# 10_Speed.net
KiCad netlist of a schematic drawn in Altium Designer
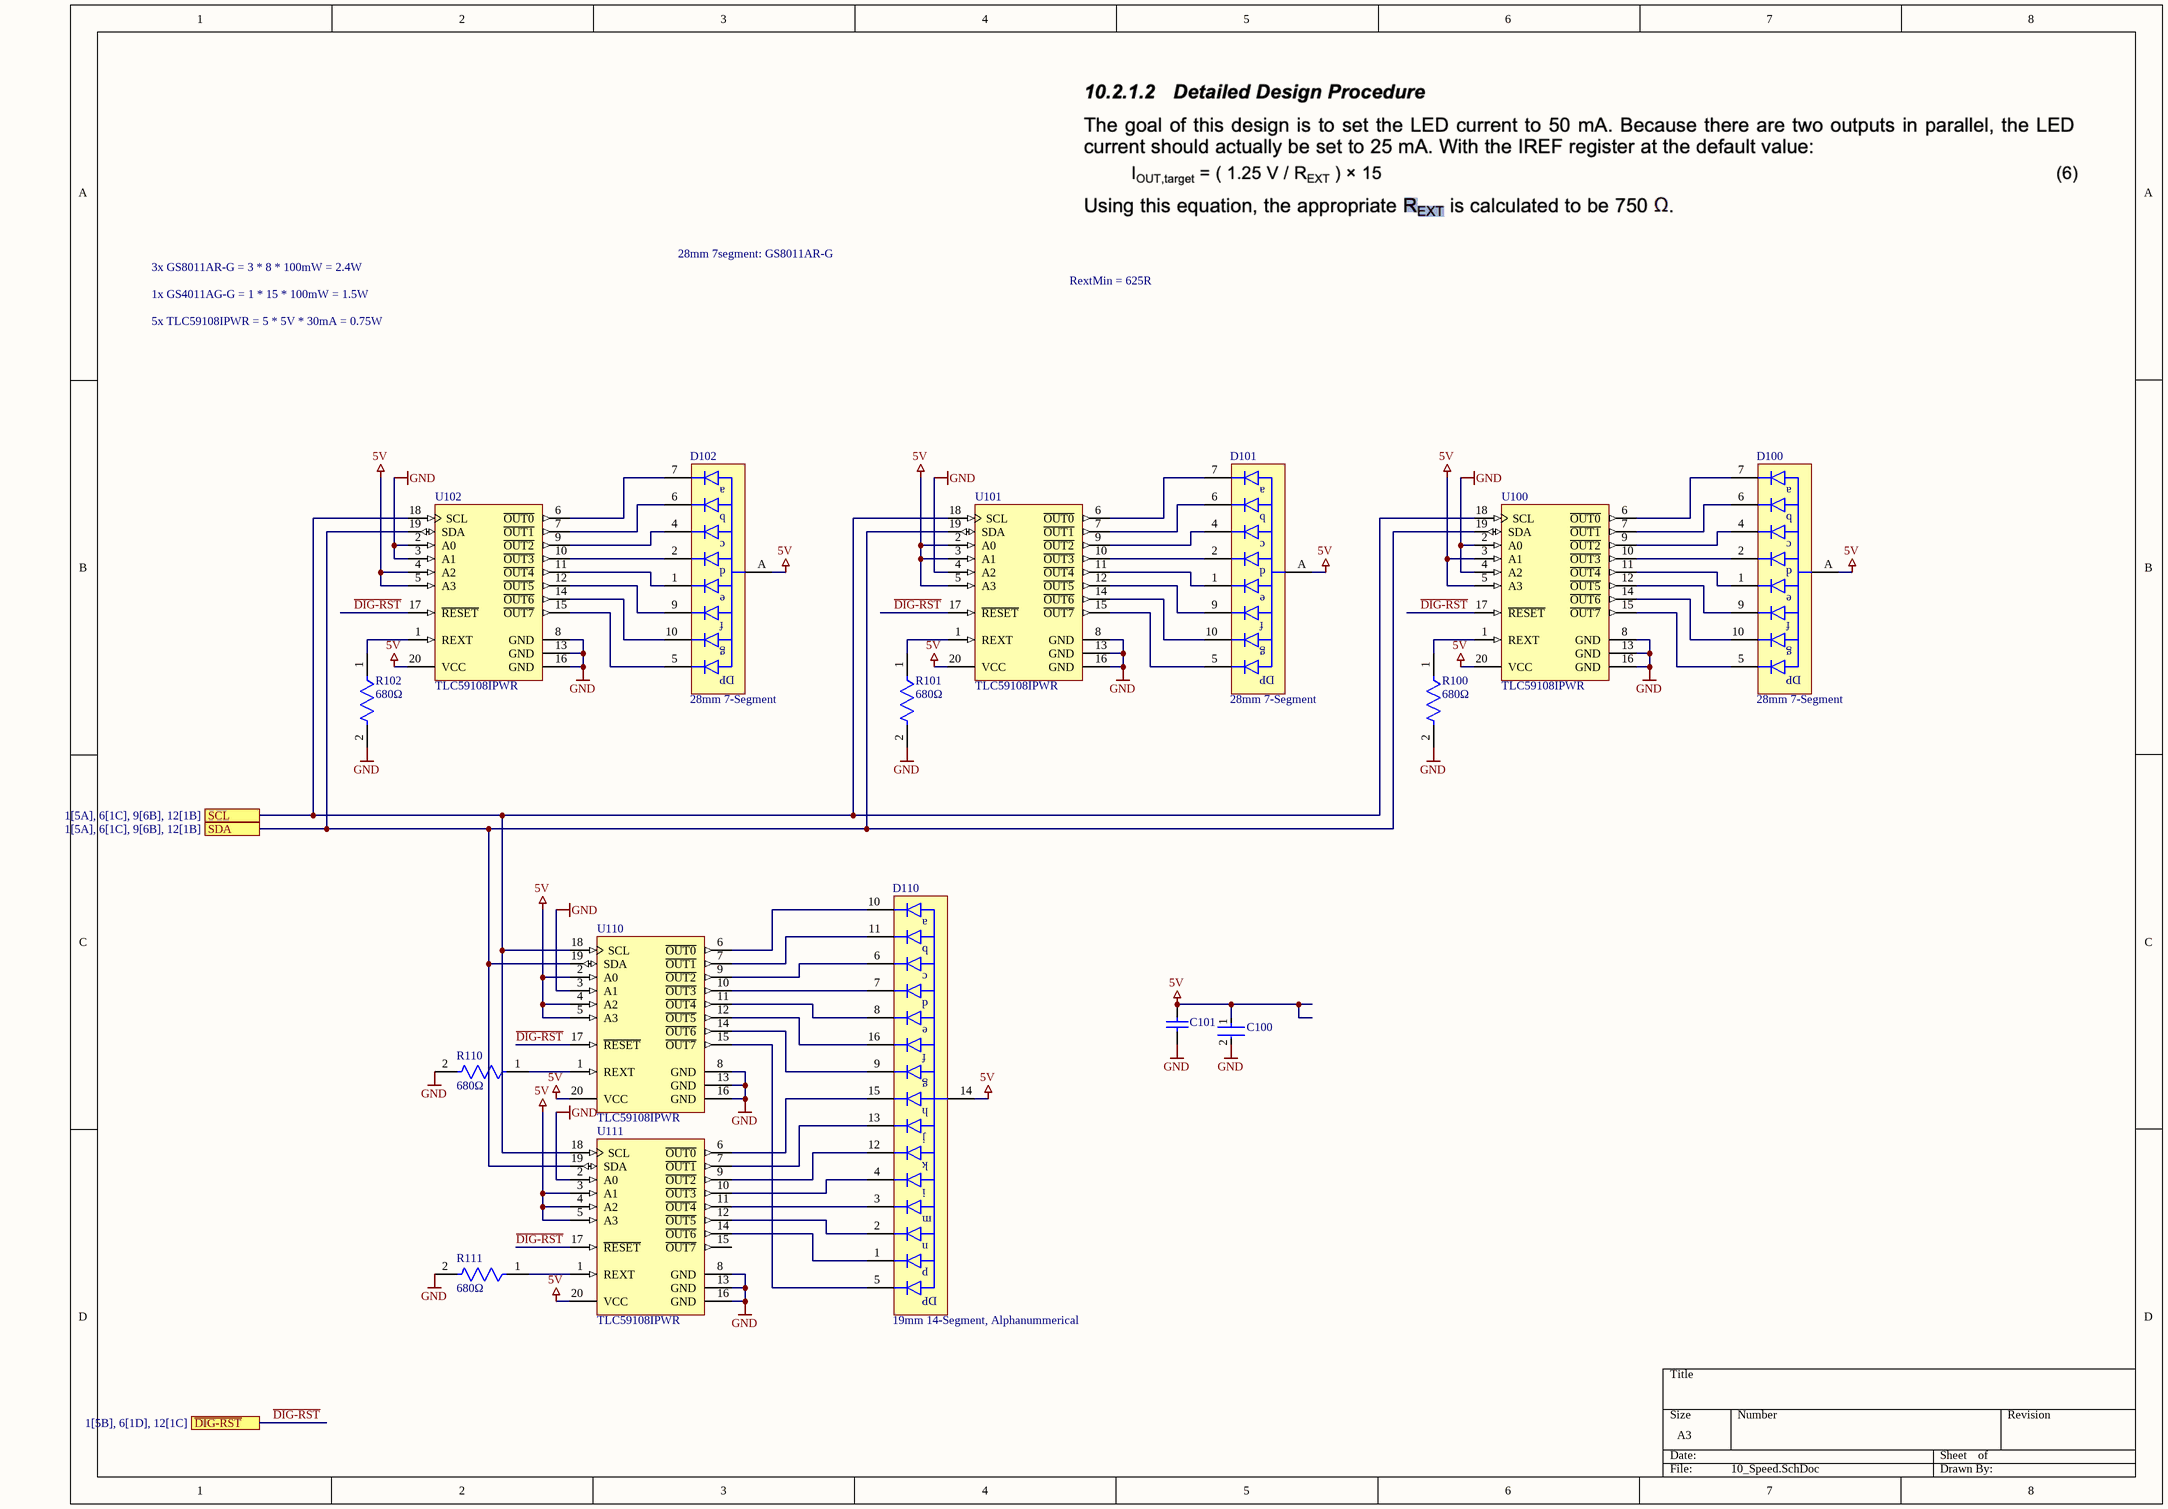
[diagram p0: 10_Speed.SchDoc]

(export (version "E")
  (design (tool "Eeschema 10.0.6"))
  (components
    (comp (ref "C100")
      (value "GMK107BJ104KAHT")
      (footprint "FP-0603-L_1_6_0_1-W_0_8_0-IPC_B")
      (description "Ceramic Capacitor Automotive 0.1uF ±10% 35V X5R 0603")
      (fields (field (name "TOLERANCE") "10%"))
      (libsource (lib "Altium Content Vault") (part "02cd4be3c70576c341d710602a673aa"))
    )
    (comp (ref "C101")
      (value "CAP 47uF 10V 1206(3216)")
      (footprint "CAPC1206(3216)190_N")
      (description "CAP 47uF 10V ±20% 1206 (3216 Metric) Thickness 1.9mm SMD")
      (fields (field (name "TOLERANCE") "Â±20%"))
      (libsource (lib "Altium Content Vault") (part "CAP"))
    )
    (comp (ref "D100")
      (value "28mm 7-Segment")
      (footprint "GS8011AR-G")
      (description "SMD, 28x16.8mm 7-Segment")
      (libsource (lib "AltiumLib_MILUTIN") (part "GS8011AR-G"))
    )
    (comp (ref "D101")
      (value "28mm 7-Segment")
      (footprint "GS8011AR-G")
      (description "SMD, 28x16.8mm 7-Segment")
      (libsource (lib "AltiumLib_MILUTIN") (part "GS8011AR-G"))
    )
    (comp (ref "D102")
      (value "28mm 7-Segment")
      (footprint "GS8011AR-G")
      (description "SMD, 28x16.8mm 7-Segment")
      (libsource (lib "AltiumLib_MILUTIN") (part "GS8011AR-G"))
    )
    (comp (ref "D110")
      (value "19mm 14-Segment, Alphanummerical")
      (footprint "GS4011AG-G")
      (description "SMD, 19x9.3mm 14-Segment, Alphanummerical")
      (libsource (lib "AltiumLib_MILUTIN") (part "GS4011AG-G"))
    )
    (comp (ref "R100")
      (value "680Ω")
      (footprint "FP-CRCW0603-e3-IPC_A")
      (description "RES Thick Film, 680Ω, 5%, 0.1W, 200ppm/°C, 0603\r\nCRCW0603680RJNEA")
      (fields (field (name "TOLERANCE") "5%"))
      (libsource (lib "Altium Content Vault") (part "1029c3af85768c4190bb7ad29bc67b5"))
    )
    (comp (ref "R101")
      (value "680Ω")
      (footprint "FP-CRCW0603-e3-IPC_A")
      (description "RES Thick Film, 680Ω, 5%, 0.1W, 200ppm/°C, 0603\r\nCRCW0603680RJNEA")
      (fields (field (name "TOLERANCE") "5%"))
      (libsource (lib "Altium Content Vault") (part "1029c3af85768c4190bb7ad29bc67b5"))
    )
    (comp (ref "R102")
      (value "680Ω")
      (footprint "FP-CRCW0603-e3-IPC_A")
      (description "RES Thick Film, 680Ω, 5%, 0.1W, 200ppm/°C, 0603\r\nCRCW0603680RJNEA")
      (fields (field (name "TOLERANCE") "5%"))
      (libsource (lib "Altium Content Vault") (part "1029c3af85768c4190bb7ad29bc67b5"))
    )
    (comp (ref "R110")
      (value "680Ω")
      (footprint "FP-CRCW0603-e3-IPC_A")
      (description "RES Thick Film, 680Ω, 5%, 0.1W, 200ppm/°C, 0603\r\nCRCW0603680RJNEA")
      (fields (field (name "TOLERANCE") "5%"))
      (libsource (lib "Altium Content Vault") (part "1029c3af85768c4190bb7ad29bc67b5"))
    )
    (comp (ref "R111")
      (value "680Ω")
      (footprint "FP-CRCW0603-e3-IPC_A")
      (description "RES Thick Film, 680Ω, 5%, 0.1W, 200ppm/°C, 0603\r\nCRCW0603680RJNEA")
      (fields (field (name "TOLERANCE") "5%"))
      (libsource (lib "Altium Content Vault") (part "1029c3af85768c4190bb7ad29bc67b5"))
    )
    (comp (ref "U100")
      (value "TLC59108IPWR")
      (footprint "PW0020A_M")
      (fields (field (name "MANUFACTURER") "Texas Instruments"))
      (libsource (lib "Altium Content Vault") (part "TI-TLC59108PW20"))
    )
    (comp (ref "U101")
      (value "TLC59108IPWR")
      (footprint "PW0020A_M")
      (fields (field (name "MANUFACTURER") "Texas Instruments"))
      (libsource (lib "Altium Content Vault") (part "TI-TLC59108PW20"))
    )
    (comp (ref "U102")
      (value "TLC59108IPWR")
      (footprint "PW0020A_M")
      (fields (field (name "MANUFACTURER") "Texas Instruments"))
      (libsource (lib "Altium Content Vault") (part "TI-TLC59108PW20"))
    )
    (comp (ref "U110")
      (value "TLC59108IPWR")
      (footprint "PW0020A_M")
      (fields (field (name "MANUFACTURER") "Texas Instruments"))
      (libsource (lib "Altium Content Vault") (part "TI-TLC59108PW20"))
    )
    (comp (ref "U111")
      (value "TLC59108IPWR")
      (footprint "PW0020A_M")
      (fields (field (name "MANUFACTURER") "Texas Instruments"))
      (libsource (lib "Altium Content Vault") (part "TI-TLC59108PW20"))
    )
  )
  (nets
    (net (code "1") (name "/SCL") (class "Default")
      (node (ref "U100") (pin "18") (pinfunction "SCL_18") (pintype "input"))
      (node (ref "U101") (pin "18") (pinfunction "SCL_18") (pintype "input"))
      (node (ref "U102") (pin "18") (pinfunction "SCL_18") (pintype "input"))
      (node (ref "U110") (pin "18") (pinfunction "SCL_18") (pintype "input"))
      (node (ref "U111") (pin "18") (pinfunction "SCL_18") (pintype "input"))
    )
    (net (code "2") (name "/SDA") (class "Default")
      (node (ref "U100") (pin "19") (pinfunction "SDA_19") (pintype "bidirectional"))
      (node (ref "U101") (pin "19") (pinfunction "SDA_19") (pintype "bidirectional"))
      (node (ref "U102") (pin "19") (pinfunction "SDA_19") (pintype "bidirectional"))
      (node (ref "U110") (pin "19") (pinfunction "SDA_19") (pintype "bidirectional"))
      (node (ref "U111") (pin "19") (pinfunction "SDA_19") (pintype "bidirectional"))
    )
    (net (code "3") (name "/~{DIG-RST}") (class "Default")
      (node (ref "U100") (pin "17") (pinfunction "~{RESET}_17") (pintype "input"))
      (node (ref "U101") (pin "17") (pinfunction "~{RESET}_17") (pintype "input"))
      (node (ref "U102") (pin "17") (pinfunction "~{RESET}_17") (pintype "input"))
      (node (ref "U110") (pin "17") (pinfunction "~{RESET}_17") (pintype "input"))
      (node (ref "U111") (pin "17") (pinfunction "~{RESET}_17") (pintype "input"))
    )
    (net (code "4") (name "5V") (class "Default")
      (node (ref "C100") (pin "1") (pinfunction "1_1") (pintype "passive"))
      (node (ref "C101") (pin "2") (pinfunction "2_2") (pintype "passive"))
      (node (ref "D100") (pin "A") (pinfunction "A_A") (pintype "passive"))
      (node (ref "D101") (pin "A") (pinfunction "A_A") (pintype "passive"))
      (node (ref "D102") (pin "A") (pinfunction "A_A") (pintype "passive"))
      (node (ref "D110") (pin "14") (pinfunction "14_14") (pintype "passive"))
      (node (ref "U100") (pin "20") (pinfunction "VCC_20") (pintype "power_in"))
      (node (ref "U100") (pin "3") (pinfunction "A1_3") (pintype "input"))
      (node (ref "U100") (pin "5") (pinfunction "A3_5") (pintype "input"))
      (node (ref "U101") (pin "2") (pinfunction "A0_2") (pintype "input"))
      (node (ref "U101") (pin "20") (pinfunction "VCC_20") (pintype "power_in"))
      (node (ref "U101") (pin "3") (pinfunction "A1_3") (pintype "input"))
      (node (ref "U101") (pin "5") (pinfunction "A3_5") (pintype "input"))
      (node (ref "U102") (pin "20") (pinfunction "VCC_20") (pintype "power_in"))
      (node (ref "U102") (pin "4") (pinfunction "A2_4") (pintype "input"))
      (node (ref "U102") (pin "5") (pinfunction "A3_5") (pintype "input"))
      (node (ref "U110") (pin "2") (pinfunction "A0_2") (pintype "input"))
      (node (ref "U110") (pin "20") (pinfunction "VCC_20") (pintype "power_in"))
      (node (ref "U110") (pin "4") (pinfunction "A2_4") (pintype "input"))
      (node (ref "U110") (pin "5") (pinfunction "A3_5") (pintype "input"))
      (node (ref "U111") (pin "20") (pinfunction "VCC_20") (pintype "power_in"))
      (node (ref "U111") (pin "3") (pinfunction "A1_3") (pintype "input"))
      (node (ref "U111") (pin "4") (pinfunction "A2_4") (pintype "input"))
      (node (ref "U111") (pin "5") (pinfunction "A3_5") (pintype "input"))
    )
    (net (code "5") (name "GND") (class "Default")
      (node (ref "C100") (pin "2") (pinfunction "2_2") (pintype "passive"))
      (node (ref "C101") (pin "1") (pinfunction "1_1") (pintype "passive"))
      (node (ref "R100") (pin "2") (pinfunction "2_2") (pintype "passive"))
      (node (ref "R101") (pin "2") (pinfunction "2_2") (pintype "passive"))
      (node (ref "R102") (pin "2") (pinfunction "2_2") (pintype "passive"))
      (node (ref "R110") (pin "2") (pinfunction "2_2") (pintype "passive"))
      (node (ref "R111") (pin "2") (pinfunction "2_2") (pintype "passive"))
      (node (ref "U100") (pin "13") (pinfunction "GND_13") (pintype "power_in"))
      (node (ref "U100") (pin "16") (pinfunction "GND_16") (pintype "power_in"))
      (node (ref "U100") (pin "2") (pinfunction "A0_2") (pintype "input"))
      (node (ref "U100") (pin "4") (pinfunction "A2_4") (pintype "input"))
      (node (ref "U100") (pin "8") (pinfunction "GND_8") (pintype "power_in"))
      (node (ref "U101") (pin "13") (pinfunction "GND_13") (pintype "power_in"))
      (node (ref "U101") (pin "16") (pinfunction "GND_16") (pintype "power_in"))
      (node (ref "U101") (pin "4") (pinfunction "A2_4") (pintype "input"))
      (node (ref "U101") (pin "8") (pinfunction "GND_8") (pintype "power_in"))
      (node (ref "U102") (pin "13") (pinfunction "GND_13") (pintype "power_in"))
      (node (ref "U102") (pin "16") (pinfunction "GND_16") (pintype "power_in"))
      (node (ref "U102") (pin "2") (pinfunction "A0_2") (pintype "input"))
      (node (ref "U102") (pin "3") (pinfunction "A1_3") (pintype "input"))
      (node (ref "U102") (pin "8") (pinfunction "GND_8") (pintype "power_in"))
      (node (ref "U110") (pin "13") (pinfunction "GND_13") (pintype "power_in"))
      (node (ref "U110") (pin "16") (pinfunction "GND_16") (pintype "power_in"))
      (node (ref "U110") (pin "3") (pinfunction "A1_3") (pintype "input"))
      (node (ref "U110") (pin "8") (pinfunction "GND_8") (pintype "power_in"))
      (node (ref "U111") (pin "13") (pinfunction "GND_13") (pintype "power_in"))
      (node (ref "U111") (pin "16") (pinfunction "GND_16") (pintype "power_in"))
      (node (ref "U111") (pin "2") (pinfunction "A0_2") (pintype "input"))
      (node (ref "U111") (pin "8") (pinfunction "GND_8") (pintype "power_in"))
    )
    (net (code "6") (name "Net-(U100-REXT)") (class "Default")
      (node (ref "R100") (pin "1") (pinfunction "1_1") (pintype "passive"))
      (node (ref "U100") (pin "1") (pinfunction "REXT_1") (pintype "input"))
    )
    (net (code "7") (name "Net-(U100-~{OUT0})") (class "Default")
      (node (ref "D100") (pin "7") (pinfunction "7_7") (pintype "passive"))
      (node (ref "U100") (pin "6") (pinfunction "~{OUT0}_6") (pintype "output"))
    )
    (net (code "8") (name "Net-(U100-~{OUT1})") (class "Default")
      (node (ref "D100") (pin "6") (pinfunction "6_6") (pintype "passive"))
      (node (ref "U100") (pin "7") (pinfunction "~{OUT1}_7") (pintype "output"))
    )
    (net (code "9") (name "Net-(U100-~{OUT2})") (class "Default")
      (node (ref "D100") (pin "4") (pinfunction "4_4") (pintype "passive"))
      (node (ref "U100") (pin "9") (pinfunction "~{OUT2}_9") (pintype "output"))
    )
    (net (code "10") (name "Net-(U100-~{OUT3})") (class "Default")
      (node (ref "D100") (pin "2") (pinfunction "2_2") (pintype "passive"))
      (node (ref "U100") (pin "10") (pinfunction "~{OUT3}_10") (pintype "output"))
    )
    (net (code "11") (name "Net-(U100-~{OUT4})") (class "Default")
      (node (ref "D100") (pin "1") (pinfunction "1_1") (pintype "passive"))
      (node (ref "U100") (pin "11") (pinfunction "~{OUT4}_11") (pintype "output"))
    )
    (net (code "12") (name "Net-(U100-~{OUT5})") (class "Default")
      (node (ref "D100") (pin "9") (pinfunction "9_9") (pintype "passive"))
      (node (ref "U100") (pin "12") (pinfunction "~{OUT5}_12") (pintype "output"))
    )
    (net (code "13") (name "Net-(U100-~{OUT6})") (class "Default")
      (node (ref "D100") (pin "10") (pinfunction "10_10") (pintype "passive"))
      (node (ref "U100") (pin "14") (pinfunction "~{OUT6}_14") (pintype "output"))
    )
    (net (code "14") (name "Net-(U100-~{OUT7})") (class "Default")
      (node (ref "D100") (pin "5") (pinfunction "5_5") (pintype "passive"))
      (node (ref "U100") (pin "15") (pinfunction "~{OUT7}_15") (pintype "output"))
    )
    (net (code "15") (name "Net-(U101-REXT)") (class "Default")
      (node (ref "R101") (pin "1") (pinfunction "1_1") (pintype "passive"))
      (node (ref "U101") (pin "1") (pinfunction "REXT_1") (pintype "input"))
    )
    (net (code "16") (name "Net-(U101-~{OUT0})") (class "Default")
      (node (ref "D101") (pin "7") (pinfunction "7_7") (pintype "passive"))
      (node (ref "U101") (pin "6") (pinfunction "~{OUT0}_6") (pintype "output"))
    )
    (net (code "17") (name "Net-(U101-~{OUT1})") (class "Default")
      (node (ref "D101") (pin "6") (pinfunction "6_6") (pintype "passive"))
      (node (ref "U101") (pin "7") (pinfunction "~{OUT1}_7") (pintype "output"))
    )
    (net (code "18") (name "Net-(U101-~{OUT2})") (class "Default")
      (node (ref "D101") (pin "4") (pinfunction "4_4") (pintype "passive"))
      (node (ref "U101") (pin "9") (pinfunction "~{OUT2}_9") (pintype "output"))
    )
    (net (code "19") (name "Net-(U101-~{OUT3})") (class "Default")
      (node (ref "D101") (pin "2") (pinfunction "2_2") (pintype "passive"))
      (node (ref "U101") (pin "10") (pinfunction "~{OUT3}_10") (pintype "output"))
    )
    (net (code "20") (name "Net-(U101-~{OUT4})") (class "Default")
      (node (ref "D101") (pin "1") (pinfunction "1_1") (pintype "passive"))
      (node (ref "U101") (pin "11") (pinfunction "~{OUT4}_11") (pintype "output"))
    )
    (net (code "21") (name "Net-(U101-~{OUT5})") (class "Default")
      (node (ref "D101") (pin "9") (pinfunction "9_9") (pintype "passive"))
      (node (ref "U101") (pin "12") (pinfunction "~{OUT5}_12") (pintype "output"))
    )
    (net (code "22") (name "Net-(U101-~{OUT6})") (class "Default")
      (node (ref "D101") (pin "10") (pinfunction "10_10") (pintype "passive"))
      (node (ref "U101") (pin "14") (pinfunction "~{OUT6}_14") (pintype "output"))
    )
    (net (code "23") (name "Net-(U101-~{OUT7})") (class "Default")
      (node (ref "D101") (pin "5") (pinfunction "5_5") (pintype "passive"))
      (node (ref "U101") (pin "15") (pinfunction "~{OUT7}_15") (pintype "output"))
    )
    (net (code "24") (name "Net-(U102-REXT)") (class "Default")
      (node (ref "R102") (pin "1") (pinfunction "1_1") (pintype "passive"))
      (node (ref "U102") (pin "1") (pinfunction "REXT_1") (pintype "input"))
    )
    (net (code "25") (name "Net-(U102-~{OUT0})") (class "Default")
      (node (ref "D102") (pin "7") (pinfunction "7_7") (pintype "passive"))
      (node (ref "U102") (pin "6") (pinfunction "~{OUT0}_6") (pintype "output"))
    )
    (net (code "26") (name "Net-(U102-~{OUT1})") (class "Default")
      (node (ref "D102") (pin "6") (pinfunction "6_6") (pintype "passive"))
      (node (ref "U102") (pin "7") (pinfunction "~{OUT1}_7") (pintype "output"))
    )
    (net (code "27") (name "Net-(U102-~{OUT2})") (class "Default")
      (node (ref "D102") (pin "4") (pinfunction "4_4") (pintype "passive"))
      (node (ref "U102") (pin "9") (pinfunction "~{OUT2}_9") (pintype "output"))
    )
    (net (code "28") (name "Net-(U102-~{OUT3})") (class "Default")
      (node (ref "D102") (pin "2") (pinfunction "2_2") (pintype "passive"))
      (node (ref "U102") (pin "10") (pinfunction "~{OUT3}_10") (pintype "output"))
    )
    (net (code "29") (name "Net-(U102-~{OUT4})") (class "Default")
      (node (ref "D102") (pin "1") (pinfunction "1_1") (pintype "passive"))
      (node (ref "U102") (pin "11") (pinfunction "~{OUT4}_11") (pintype "output"))
    )
    (net (code "30") (name "Net-(U102-~{OUT5})") (class "Default")
      (node (ref "D102") (pin "9") (pinfunction "9_9") (pintype "passive"))
      (node (ref "U102") (pin "12") (pinfunction "~{OUT5}_12") (pintype "output"))
    )
    (net (code "31") (name "Net-(U102-~{OUT6})") (class "Default")
      (node (ref "D102") (pin "10") (pinfunction "10_10") (pintype "passive"))
      (node (ref "U102") (pin "14") (pinfunction "~{OUT6}_14") (pintype "output"))
    )
    (net (code "32") (name "Net-(U102-~{OUT7})") (class "Default")
      (node (ref "D102") (pin "5") (pinfunction "5_5") (pintype "passive"))
      (node (ref "U102") (pin "15") (pinfunction "~{OUT7}_15") (pintype "output"))
    )
    (net (code "33") (name "Net-(U110-REXT)") (class "Default")
      (node (ref "R110") (pin "1") (pinfunction "1_1") (pintype "passive"))
      (node (ref "U110") (pin "1") (pinfunction "REXT_1") (pintype "input"))
    )
    (net (code "34") (name "Net-(U110-~{OUT0})") (class "Default")
      (node (ref "D110") (pin "10") (pinfunction "10_10") (pintype "passive"))
      (node (ref "U110") (pin "6") (pinfunction "~{OUT0}_6") (pintype "output"))
    )
    (net (code "35") (name "Net-(U110-~{OUT1})") (class "Default")
      (node (ref "D110") (pin "11") (pinfunction "11_11") (pintype "passive"))
      (node (ref "U110") (pin "7") (pinfunction "~{OUT1}_7") (pintype "output"))
    )
    (net (code "36") (name "Net-(U110-~{OUT2})") (class "Default")
      (node (ref "D110") (pin "6") (pinfunction "6_6") (pintype "passive"))
      (node (ref "U110") (pin "9") (pinfunction "~{OUT2}_9") (pintype "output"))
    )
    (net (code "37") (name "Net-(U110-~{OUT3})") (class "Default")
      (node (ref "D110") (pin "7") (pinfunction "7_7") (pintype "passive"))
      (node (ref "U110") (pin "10") (pinfunction "~{OUT3}_10") (pintype "output"))
    )
    (net (code "38") (name "Net-(U110-~{OUT4})") (class "Default")
      (node (ref "D110") (pin "8") (pinfunction "8_8") (pintype "passive"))
      (node (ref "U110") (pin "11") (pinfunction "~{OUT4}_11") (pintype "output"))
    )
    (net (code "39") (name "Net-(U110-~{OUT5})") (class "Default")
      (node (ref "D110") (pin "16") (pinfunction "16_16") (pintype "passive"))
      (node (ref "U110") (pin "12") (pinfunction "~{OUT5}_12") (pintype "output"))
    )
    (net (code "40") (name "Net-(U110-~{OUT6})") (class "Default")
      (node (ref "D110") (pin "9") (pinfunction "9_9") (pintype "passive"))
      (node (ref "U110") (pin "14") (pinfunction "~{OUT6}_14") (pintype "output"))
    )
    (net (code "41") (name "Net-(U110-~{OUT7})") (class "Default")
      (node (ref "D110") (pin "5") (pinfunction "5_5") (pintype "passive"))
      (node (ref "U110") (pin "15") (pinfunction "~{OUT7}_15") (pintype "output"))
    )
    (net (code "42") (name "Net-(U111-REXT)") (class "Default")
      (node (ref "R111") (pin "1") (pinfunction "1_1") (pintype "passive"))
      (node (ref "U111") (pin "1") (pinfunction "REXT_1") (pintype "input"))
    )
    (net (code "43") (name "Net-(U111-~{OUT0})") (class "Default")
      (node (ref "D110") (pin "15") (pinfunction "15_15") (pintype "passive"))
      (node (ref "U111") (pin "6") (pinfunction "~{OUT0}_6") (pintype "output"))
    )
    (net (code "44") (name "Net-(U111-~{OUT1})") (class "Default")
      (node (ref "D110") (pin "13") (pinfunction "13_13") (pintype "passive"))
      (node (ref "U111") (pin "7") (pinfunction "~{OUT1}_7") (pintype "output"))
    )
    (net (code "45") (name "Net-(U111-~{OUT2})") (class "Default")
      (node (ref "D110") (pin "12") (pinfunction "12_12") (pintype "passive"))
      (node (ref "U111") (pin "9") (pinfunction "~{OUT2}_9") (pintype "output"))
    )
    (net (code "46") (name "Net-(U111-~{OUT3})") (class "Default")
      (node (ref "D110") (pin "4") (pinfunction "4_4") (pintype "passive"))
      (node (ref "U111") (pin "10") (pinfunction "~{OUT3}_10") (pintype "output"))
    )
    (net (code "47") (name "Net-(U111-~{OUT4})") (class "Default")
      (node (ref "D110") (pin "3") (pinfunction "3_3") (pintype "passive"))
      (node (ref "U111") (pin "11") (pinfunction "~{OUT4}_11") (pintype "output"))
    )
    (net (code "48") (name "Net-(U111-~{OUT5})") (class "Default")
      (node (ref "D110") (pin "2") (pinfunction "2_2") (pintype "passive"))
      (node (ref "U111") (pin "12") (pinfunction "~{OUT5}_12") (pintype "output"))
    )
    (net (code "49") (name "Net-(U111-~{OUT6})") (class "Default")
      (node (ref "D110") (pin "1") (pinfunction "1_1") (pintype "passive"))
      (node (ref "U111") (pin "14") (pinfunction "~{OUT6}_14") (pintype "output"))
    )
    (net (code "50") (name "unconnected-(U111-~{OUT7}-Pad15)") (class "Default")
      (node (ref "U111") (pin "15") (pinfunction "~{OUT7}_15") (pintype "output"))
    )
  )
)
